# resistors.net
KiCad netlist of a schematic drawn in Altium Designer
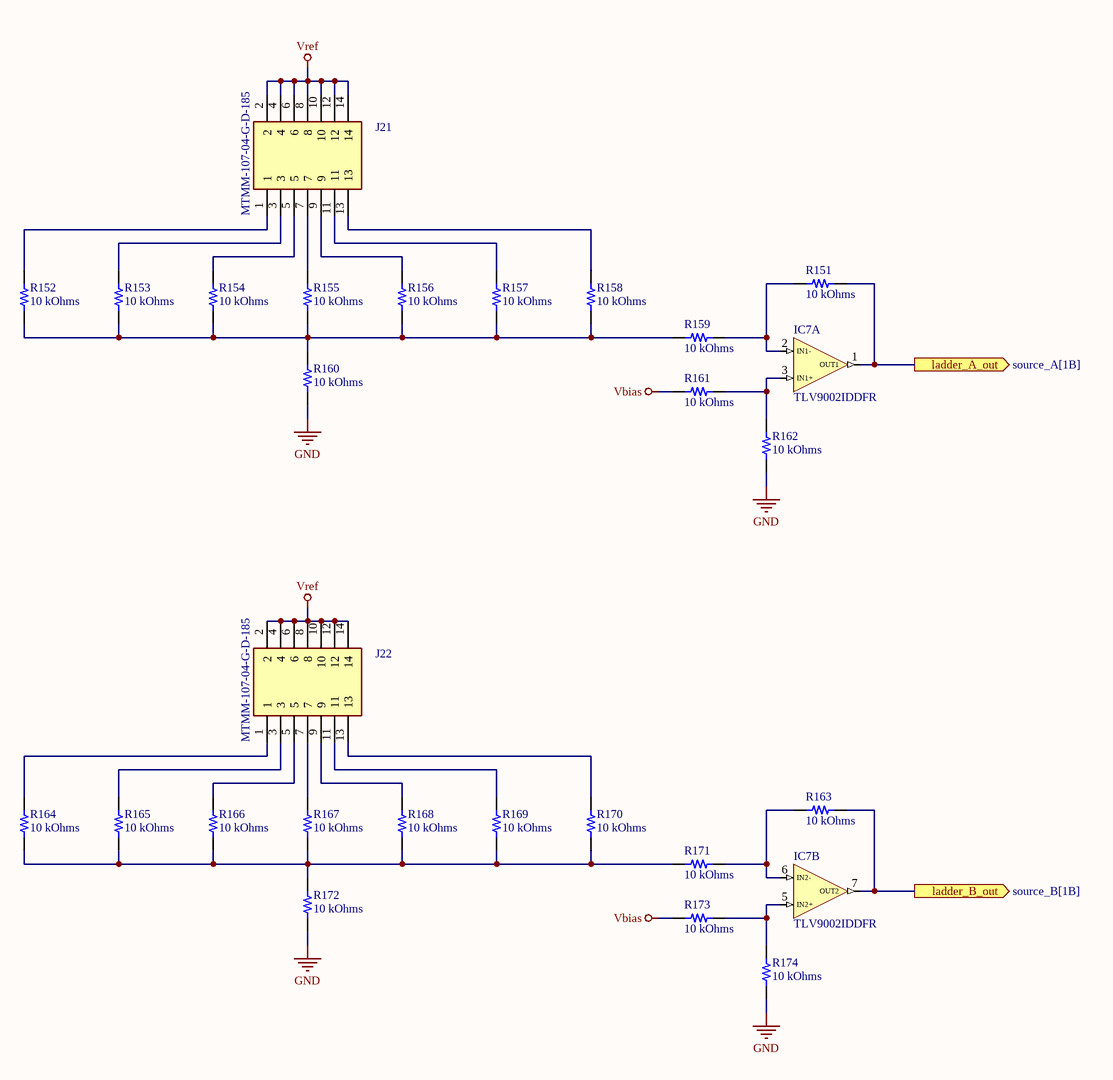
[diagram p0: resistors.SchDoc]

(export (version "E")
  (design (tool "Eeschema 10.0.6"))
  (components
    (comp (ref "IC7")
      (value "TLV9002IDDFR")
      (footprint "SOT65P280X110-8N")
      (description "Integrated Circuit")
      (fields (field (name "MOUSER PART NUMBER") "595-TLV9002IDDFR"))
      (libsource (lib "za_koncar") (part "TLV9002IDDFR"))
    )
    (comp (ref "J21")
      (value "MTMM-107-04-G-D-185")
      (footprint "MTMM10704GD185")
      (description "Connector")
      (fields (field (name "MOUSER PART NUMBER") "200-MTMM10704GD185"))
      (libsource (lib "za_koncar") (part "MTMM-107-04-G-D-185"))
    )
    (comp (ref "J22")
      (value "MTMM-107-04-G-D-185")
      (footprint "MTMM10704GD185")
      (description "Connector")
      (fields (field (name "MOUSER PART NUMBER") "200-MTMM10704GD185"))
      (libsource (lib "za_koncar") (part "MTMM-107-04-G-D-185"))
    )
    (comp (ref "R151")
      (value "10 kOhms")
      (footprint "YAGEO RES 1206_3216")
      (description "RES SMD 10K OHM 1% 1/4W 1206")
      (fields (field (name "PART NUMBER") "RT1206FRE0710KL") (field (name "MANUFACTURER") "Yageo"))
      (libsource (lib "Celestial Altium Library - altium_library") (part "Resistor"))
    )
    (comp (ref "R152")
      (value "10 kOhms")
      (footprint "YAGEO RES 1206_3216")
      (description "RES SMD 10K OHM 1% 1/4W 1206")
      (fields (field (name "PART NUMBER") "RT1206FRE0710KL") (field (name "MANUFACTURER") "Yageo"))
      (libsource (lib "Celestial Altium Library - altium_library") (part "Resistor"))
    )
    (comp (ref "R153")
      (value "10 kOhms")
      (footprint "YAGEO RES 1206_3216")
      (description "RES SMD 10K OHM 1% 1/4W 1206")
      (fields (field (name "PART NUMBER") "RT1206FRE0710KL") (field (name "MANUFACTURER") "Yageo"))
      (libsource (lib "Celestial Altium Library - altium_library") (part "Resistor"))
    )
    (comp (ref "R154")
      (value "10 kOhms")
      (footprint "YAGEO RES 1206_3216")
      (description "RES SMD 10K OHM 1% 1/4W 1206")
      (fields (field (name "PART NUMBER") "RT1206FRE0710KL") (field (name "MANUFACTURER") "Yageo"))
      (libsource (lib "Celestial Altium Library - altium_library") (part "Resistor"))
    )
    (comp (ref "R155")
      (value "10 kOhms")
      (footprint "YAGEO RES 1206_3216")
      (description "RES SMD 10K OHM 1% 1/4W 1206")
      (fields (field (name "PART NUMBER") "RT1206FRE0710KL") (field (name "MANUFACTURER") "Yageo"))
      (libsource (lib "Celestial Altium Library - altium_library") (part "Resistor"))
    )
    (comp (ref "R156")
      (value "10 kOhms")
      (footprint "YAGEO RES 1206_3216")
      (description "RES SMD 10K OHM 1% 1/4W 1206")
      (fields (field (name "PART NUMBER") "RT1206FRE0710KL") (field (name "MANUFACTURER") "Yageo"))
      (libsource (lib "Celestial Altium Library - altium_library") (part "Resistor"))
    )
    (comp (ref "R157")
      (value "10 kOhms")
      (footprint "YAGEO RES 1206_3216")
      (description "RES SMD 10K OHM 1% 1/4W 1206")
      (fields (field (name "PART NUMBER") "RT1206FRE0710KL") (field (name "MANUFACTURER") "Yageo"))
      (libsource (lib "Celestial Altium Library - altium_library") (part "Resistor"))
    )
    (comp (ref "R158")
      (value "10 kOhms")
      (footprint "YAGEO RES 1206_3216")
      (description "RES SMD 10K OHM 1% 1/4W 1206")
      (fields (field (name "PART NUMBER") "RT1206FRE0710KL") (field (name "MANUFACTURER") "Yageo"))
      (libsource (lib "Celestial Altium Library - altium_library") (part "Resistor"))
    )
    (comp (ref "R159")
      (value "10 kOhms")
      (footprint "YAGEO RES 1206_3216")
      (description "RES SMD 10K OHM 1% 1/4W 1206")
      (fields (field (name "PART NUMBER") "RT1206FRE0710KL") (field (name "MANUFACTURER") "Yageo"))
      (libsource (lib "Celestial Altium Library - altium_library") (part "Resistor"))
    )
    (comp (ref "R160")
      (value "10 kOhms")
      (footprint "YAGEO RES 1206_3216")
      (description "RES SMD 10K OHM 1% 1/4W 1206")
      (fields (field (name "PART NUMBER") "RT1206FRE0710KL") (field (name "MANUFACTURER") "Yageo"))
      (libsource (lib "Celestial Altium Library - altium_library") (part "Resistor"))
    )
    (comp (ref "R161")
      (value "10 kOhms")
      (footprint "YAGEO RES 1206_3216")
      (description "RES SMD 10K OHM 1% 1/4W 1206")
      (fields (field (name "PART NUMBER") "RT1206FRE0710KL") (field (name "MANUFACTURER") "Yageo"))
      (libsource (lib "Celestial Altium Library - altium_library") (part "Resistor"))
    )
    (comp (ref "R162")
      (value "10 kOhms")
      (footprint "YAGEO RES 1206_3216")
      (description "RES SMD 10K OHM 1% 1/4W 1206")
      (fields (field (name "PART NUMBER") "RT1206FRE0710KL") (field (name "MANUFACTURER") "Yageo"))
      (libsource (lib "Celestial Altium Library - altium_library") (part "Resistor"))
    )
    (comp (ref "R163")
      (value "10 kOhms")
      (footprint "YAGEO RES 1206_3216")
      (description "RES SMD 10K OHM 1% 1/4W 1206")
      (fields (field (name "PART NUMBER") "RT1206FRE0710KL") (field (name "MANUFACTURER") "Yageo"))
      (libsource (lib "Celestial Altium Library - altium_library") (part "Resistor"))
    )
    (comp (ref "R164")
      (value "10 kOhms")
      (footprint "YAGEO RES 1206_3216")
      (description "RES SMD 10K OHM 1% 1/4W 1206")
      (fields (field (name "PART NUMBER") "RT1206FRE0710KL") (field (name "MANUFACTURER") "Yageo"))
      (libsource (lib "Celestial Altium Library - altium_library") (part "Resistor"))
    )
    (comp (ref "R165")
      (value "10 kOhms")
      (footprint "YAGEO RES 1206_3216")
      (description "RES SMD 10K OHM 1% 1/4W 1206")
      (fields (field (name "PART NUMBER") "RT1206FRE0710KL") (field (name "MANUFACTURER") "Yageo"))
      (libsource (lib "Celestial Altium Library - altium_library") (part "Resistor"))
    )
    (comp (ref "R166")
      (value "10 kOhms")
      (footprint "YAGEO RES 1206_3216")
      (description "RES SMD 10K OHM 1% 1/4W 1206")
      (fields (field (name "PART NUMBER") "RT1206FRE0710KL") (field (name "MANUFACTURER") "Yageo"))
      (libsource (lib "Celestial Altium Library - altium_library") (part "Resistor"))
    )
    (comp (ref "R167")
      (value "10 kOhms")
      (footprint "YAGEO RES 1206_3216")
      (description "RES SMD 10K OHM 1% 1/4W 1206")
      (fields (field (name "PART NUMBER") "RT1206FRE0710KL") (field (name "MANUFACTURER") "Yageo"))
      (libsource (lib "Celestial Altium Library - altium_library") (part "Resistor"))
    )
    (comp (ref "R168")
      (value "10 kOhms")
      (footprint "YAGEO RES 1206_3216")
      (description "RES SMD 10K OHM 1% 1/4W 1206")
      (fields (field (name "PART NUMBER") "RT1206FRE0710KL") (field (name "MANUFACTURER") "Yageo"))
      (libsource (lib "Celestial Altium Library - altium_library") (part "Resistor"))
    )
    (comp (ref "R169")
      (value "10 kOhms")
      (footprint "YAGEO RES 1206_3216")
      (description "RES SMD 10K OHM 1% 1/4W 1206")
      (fields (field (name "PART NUMBER") "RT1206FRE0710KL") (field (name "MANUFACTURER") "Yageo"))
      (libsource (lib "Celestial Altium Library - altium_library") (part "Resistor"))
    )
    (comp (ref "R170")
      (value "10 kOhms")
      (footprint "YAGEO RES 1206_3216")
      (description "RES SMD 10K OHM 1% 1/4W 1206")
      (fields (field (name "PART NUMBER") "RT1206FRE0710KL") (field (name "MANUFACTURER") "Yageo"))
      (libsource (lib "Celestial Altium Library - altium_library") (part "Resistor"))
    )
    (comp (ref "R171")
      (value "10 kOhms")
      (footprint "YAGEO RES 1206_3216")
      (description "RES SMD 10K OHM 1% 1/4W 1206")
      (fields (field (name "PART NUMBER") "RT1206FRE0710KL") (field (name "MANUFACTURER") "Yageo"))
      (libsource (lib "Celestial Altium Library - altium_library") (part "Resistor"))
    )
    (comp (ref "R172")
      (value "10 kOhms")
      (footprint "YAGEO RES 1206_3216")
      (description "RES SMD 10K OHM 1% 1/4W 1206")
      (fields (field (name "PART NUMBER") "RT1206FRE0710KL") (field (name "MANUFACTURER") "Yageo"))
      (libsource (lib "Celestial Altium Library - altium_library") (part "Resistor"))
    )
    (comp (ref "R173")
      (value "10 kOhms")
      (footprint "YAGEO RES 1206_3216")
      (description "RES SMD 10K OHM 1% 1/4W 1206")
      (fields (field (name "PART NUMBER") "RT1206FRE0710KL") (field (name "MANUFACTURER") "Yageo"))
      (libsource (lib "Celestial Altium Library - altium_library") (part "Resistor"))
    )
    (comp (ref "R174")
      (value "10 kOhms")
      (footprint "YAGEO RES 1206_3216")
      (description "RES SMD 10K OHM 1% 1/4W 1206")
      (fields (field (name "PART NUMBER") "RT1206FRE0710KL") (field (name "MANUFACTURER") "Yageo"))
      (libsource (lib "Celestial Altium Library - altium_library") (part "Resistor"))
    )
  )
  (nets
    (net (code "1") (name "/ladder_A_out") (class "Default")
      (node (ref "IC7") (pin "1") (pinfunction "OUT1_1") (pintype "output"))
      (node (ref "R151") (pin "1") (pinfunction "1_1") (pintype "passive"))
    )
    (net (code "2") (name "/ladder_B_out") (class "Default")
      (node (ref "IC7") (pin "7") (pinfunction "OUT2_7") (pintype "output"))
      (node (ref "R163") (pin "1") (pinfunction "1_1") (pintype "passive"))
    )
    (net (code "3") (name "GND") (class "Default")
      (node (ref "R160") (pin "1") (pinfunction "1_1") (pintype "passive"))
      (node (ref "R162") (pin "1") (pinfunction "1_1") (pintype "passive"))
      (node (ref "R172") (pin "1") (pinfunction "1_1") (pintype "passive"))
      (node (ref "R174") (pin "1") (pinfunction "1_1") (pintype "passive"))
    )
    (net (code "4") (name "Net-(IC7A-IN1+)") (class "Default")
      (node (ref "IC7") (pin "3") (pinfunction "IN1+_3") (pintype "input"))
      (node (ref "R161") (pin "1") (pinfunction "1_1") (pintype "passive"))
      (node (ref "R162") (pin "2") (pinfunction "2_2") (pintype "passive"))
    )
    (net (code "5") (name "Net-(IC7A-IN1-)") (class "Default")
      (node (ref "IC7") (pin "2") (pinfunction "IN1-_2") (pintype "input"))
      (node (ref "R151") (pin "2") (pinfunction "2_2") (pintype "passive"))
      (node (ref "R159") (pin "1") (pinfunction "1_1") (pintype "passive"))
    )
    (net (code "6") (name "Net-(IC7B-IN2+)") (class "Default")
      (node (ref "IC7") (pin "5") (pinfunction "IN2+_5") (pintype "input"))
      (node (ref "R173") (pin "1") (pinfunction "1_1") (pintype "passive"))
      (node (ref "R174") (pin "2") (pinfunction "2_2") (pintype "passive"))
    )
    (net (code "7") (name "Net-(IC7B-IN2-)") (class "Default")
      (node (ref "IC7") (pin "6") (pinfunction "IN2-_6") (pintype "input"))
      (node (ref "R163") (pin "2") (pinfunction "2_2") (pintype "passive"))
      (node (ref "R171") (pin "1") (pinfunction "1_1") (pintype "passive"))
    )
    (net (code "8") (name "Net-(J21-Pad1)") (class "Default")
      (node (ref "J21") (pin "1") (pinfunction "1_1") (pintype "passive"))
      (node (ref "R152") (pin "2") (pinfunction "2_2") (pintype "passive"))
    )
    (net (code "9") (name "Net-(J21-Pad3)") (class "Default")
      (node (ref "J21") (pin "3") (pinfunction "3_3") (pintype "passive"))
      (node (ref "R153") (pin "2") (pinfunction "2_2") (pintype "passive"))
    )
    (net (code "10") (name "Net-(J21-Pad5)") (class "Default")
      (node (ref "J21") (pin "5") (pinfunction "5_5") (pintype "passive"))
      (node (ref "R154") (pin "2") (pinfunction "2_2") (pintype "passive"))
    )
    (net (code "11") (name "Net-(J21-Pad7)") (class "Default")
      (node (ref "J21") (pin "7") (pinfunction "7_7") (pintype "passive"))
      (node (ref "R155") (pin "2") (pinfunction "2_2") (pintype "passive"))
    )
    (net (code "12") (name "Net-(J21-Pad9)") (class "Default")
      (node (ref "J21") (pin "9") (pinfunction "9_9") (pintype "passive"))
      (node (ref "R156") (pin "2") (pinfunction "2_2") (pintype "passive"))
    )
    (net (code "13") (name "Net-(J21-Pad11)") (class "Default")
      (node (ref "J21") (pin "11") (pinfunction "11_11") (pintype "passive"))
      (node (ref "R157") (pin "2") (pinfunction "2_2") (pintype "passive"))
    )
    (net (code "14") (name "Net-(J21-Pad13)") (class "Default")
      (node (ref "J21") (pin "13") (pinfunction "13_13") (pintype "passive"))
      (node (ref "R158") (pin "2") (pinfunction "2_2") (pintype "passive"))
    )
    (net (code "15") (name "Net-(J22-Pad1)") (class "Default")
      (node (ref "J22") (pin "1") (pinfunction "1_1") (pintype "passive"))
      (node (ref "R164") (pin "2") (pinfunction "2_2") (pintype "passive"))
    )
    (net (code "16") (name "Net-(J22-Pad3)") (class "Default")
      (node (ref "J22") (pin "3") (pinfunction "3_3") (pintype "passive"))
      (node (ref "R165") (pin "2") (pinfunction "2_2") (pintype "passive"))
    )
    (net (code "17") (name "Net-(J22-Pad5)") (class "Default")
      (node (ref "J22") (pin "5") (pinfunction "5_5") (pintype "passive"))
      (node (ref "R166") (pin "2") (pinfunction "2_2") (pintype "passive"))
    )
    (net (code "18") (name "Net-(J22-Pad7)") (class "Default")
      (node (ref "J22") (pin "7") (pinfunction "7_7") (pintype "passive"))
      (node (ref "R167") (pin "2") (pinfunction "2_2") (pintype "passive"))
    )
    (net (code "19") (name "Net-(J22-Pad9)") (class "Default")
      (node (ref "J22") (pin "9") (pinfunction "9_9") (pintype "passive"))
      (node (ref "R168") (pin "2") (pinfunction "2_2") (pintype "passive"))
    )
    (net (code "20") (name "Net-(J22-Pad11)") (class "Default")
      (node (ref "J22") (pin "11") (pinfunction "11_11") (pintype "passive"))
      (node (ref "R169") (pin "2") (pinfunction "2_2") (pintype "passive"))
    )
    (net (code "21") (name "Net-(J22-Pad13)") (class "Default")
      (node (ref "J22") (pin "13") (pinfunction "13_13") (pintype "passive"))
      (node (ref "R170") (pin "2") (pinfunction "2_2") (pintype "passive"))
    )
    (net (code "22") (name "Net-(R152-Pad1)") (class "Default")
      (node (ref "R152") (pin "1") (pinfunction "1_1") (pintype "passive"))
      (node (ref "R153") (pin "1") (pinfunction "1_1") (pintype "passive"))
      (node (ref "R154") (pin "1") (pinfunction "1_1") (pintype "passive"))
      (node (ref "R155") (pin "1") (pinfunction "1_1") (pintype "passive"))
      (node (ref "R156") (pin "1") (pinfunction "1_1") (pintype "passive"))
      (node (ref "R157") (pin "1") (pinfunction "1_1") (pintype "passive"))
      (node (ref "R158") (pin "1") (pinfunction "1_1") (pintype "passive"))
      (node (ref "R159") (pin "2") (pinfunction "2_2") (pintype "passive"))
      (node (ref "R160") (pin "2") (pinfunction "2_2") (pintype "passive"))
    )
    (net (code "23") (name "Net-(R164-Pad1)") (class "Default")
      (node (ref "R164") (pin "1") (pinfunction "1_1") (pintype "passive"))
      (node (ref "R165") (pin "1") (pinfunction "1_1") (pintype "passive"))
      (node (ref "R166") (pin "1") (pinfunction "1_1") (pintype "passive"))
      (node (ref "R167") (pin "1") (pinfunction "1_1") (pintype "passive"))
      (node (ref "R168") (pin "1") (pinfunction "1_1") (pintype "passive"))
      (node (ref "R169") (pin "1") (pinfunction "1_1") (pintype "passive"))
      (node (ref "R170") (pin "1") (pinfunction "1_1") (pintype "passive"))
      (node (ref "R171") (pin "2") (pinfunction "2_2") (pintype "passive"))
      (node (ref "R172") (pin "2") (pinfunction "2_2") (pintype "passive"))
    )
    (net (code "24") (name "Vbias") (class "Default")
      (node (ref "R161") (pin "2") (pinfunction "2_2") (pintype "passive"))
      (node (ref "R173") (pin "2") (pinfunction "2_2") (pintype "passive"))
    )
    (net (code "25") (name "Vref") (class "Default")
      (node (ref "J21") (pin "10") (pinfunction "10_10") (pintype "passive"))
      (node (ref "J21") (pin "12") (pinfunction "12_12") (pintype "passive"))
      (node (ref "J21") (pin "14") (pinfunction "14_14") (pintype "passive"))
      (node (ref "J21") (pin "2") (pinfunction "2_2") (pintype "passive"))
      (node (ref "J21") (pin "4") (pinfunction "4_4") (pintype "passive"))
      (node (ref "J21") (pin "6") (pinfunction "6_6") (pintype "passive"))
      (node (ref "J21") (pin "8") (pinfunction "8_8") (pintype "passive"))
      (node (ref "J22") (pin "10") (pinfunction "10_10") (pintype "passive"))
      (node (ref "J22") (pin "12") (pinfunction "12_12") (pintype "passive"))
      (node (ref "J22") (pin "14") (pinfunction "14_14") (pintype "passive"))
      (node (ref "J22") (pin "2") (pinfunction "2_2") (pintype "passive"))
      (node (ref "J22") (pin "4") (pinfunction "4_4") (pintype "passive"))
      (node (ref "J22") (pin "6") (pinfunction "6_6") (pintype "passive"))
      (node (ref "J22") (pin "8") (pinfunction "8_8") (pintype "passive"))
    )
  )
)
